# board.net
KiCad netlist of a schematic drawn in EAGLE
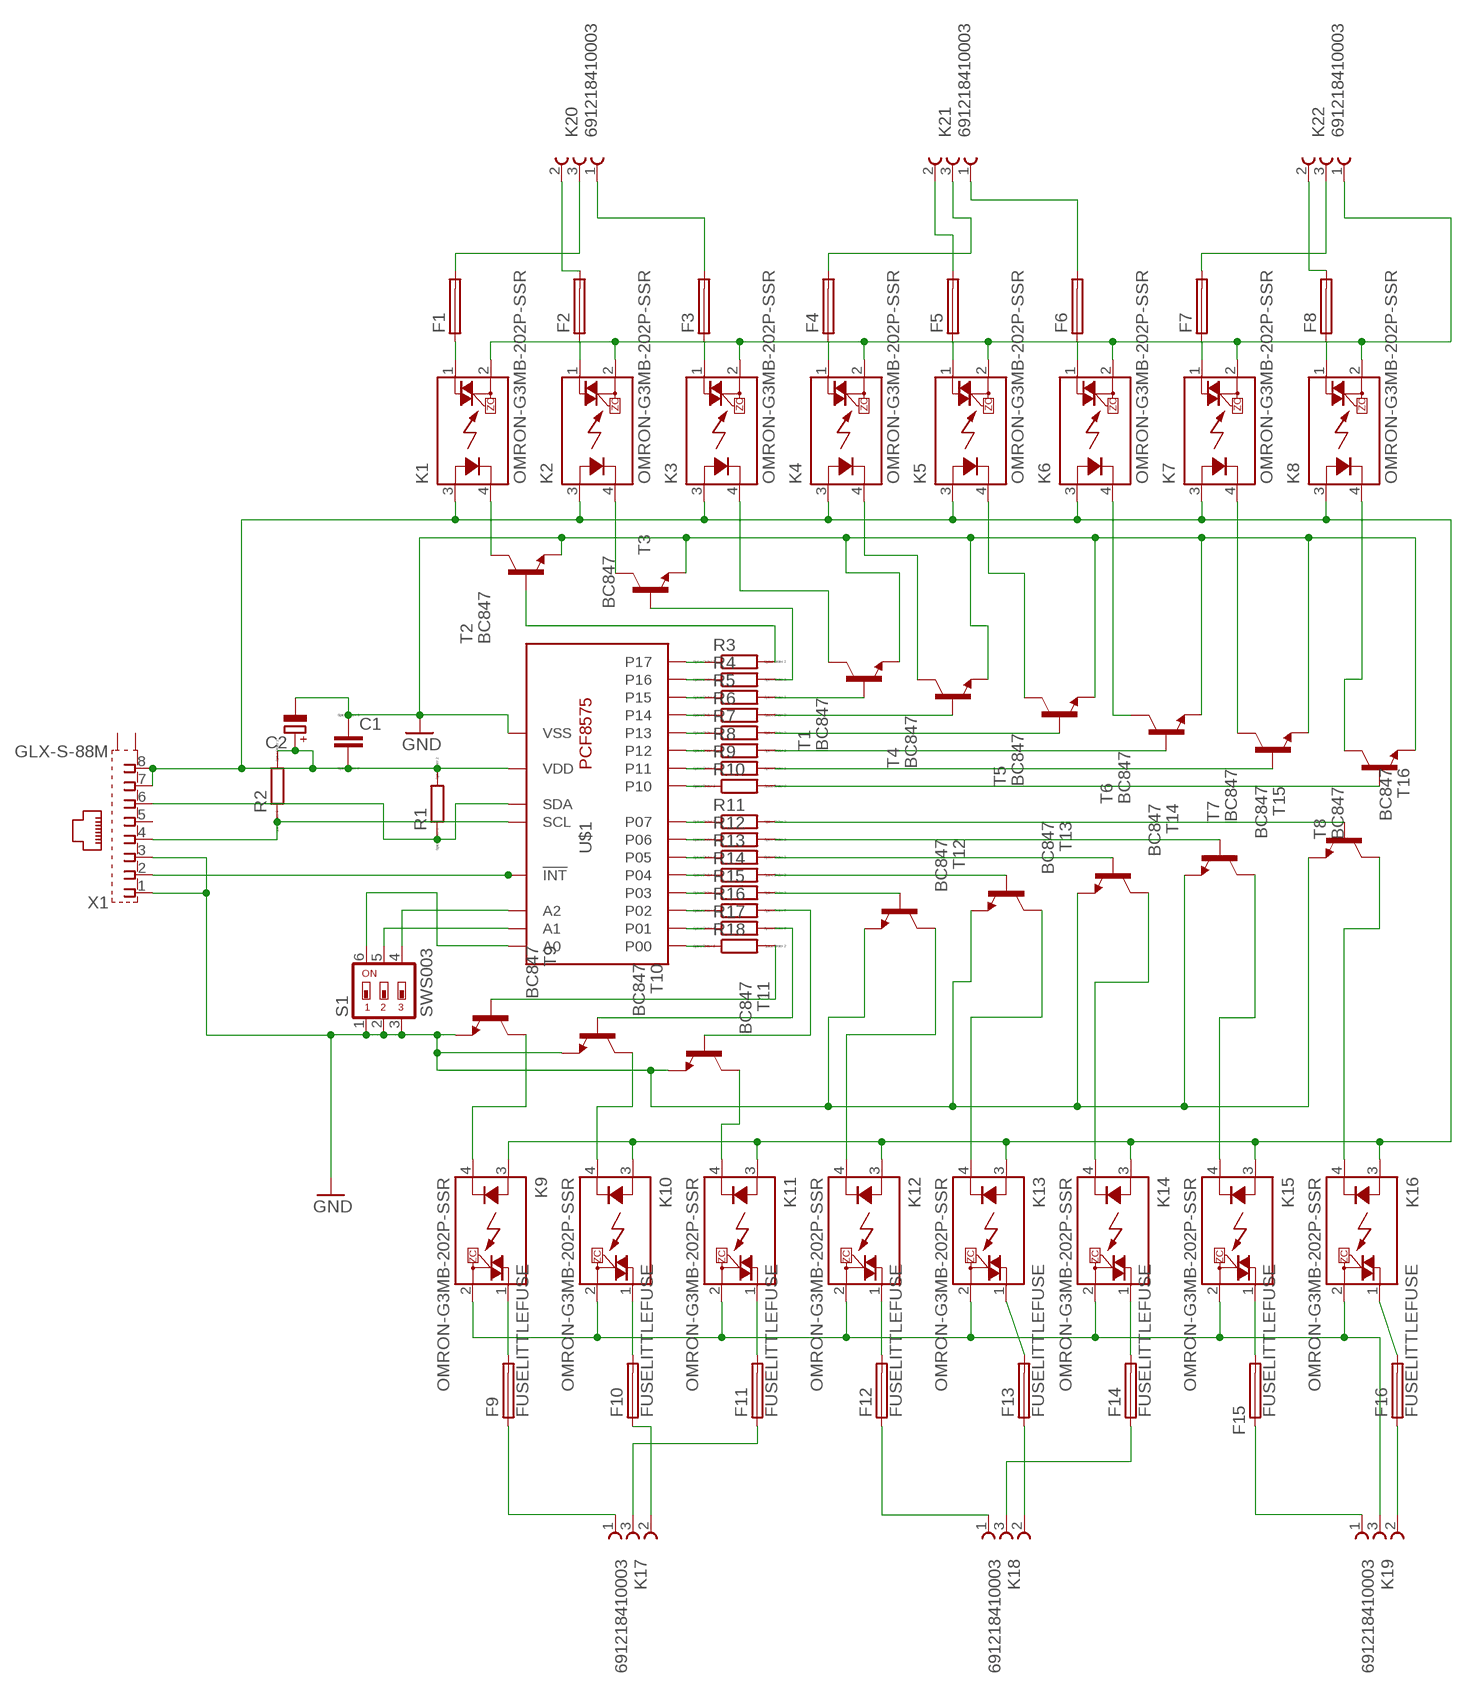
[diagram p0: schematic, sheet 1]

(export (version "E")
  (design (tool "Eeschema 10.0.6"))
  (components
    (comp (ref "C1")
      (value "CC1206")
      (footprint "eagle-import:C1206")
      (libsource (lib "eagle-import") (part "CC1206"))
    )
    (comp (ref "C2")
      (value "CPOL-EU150CLZ-0810")
      (footprint "eagle-import:150CLZ-0810")
      (libsource (lib "eagle-import") (part "CPOL-EU150CLZ-0810"))
    )
    (comp (ref "F1")
      (value "FUSELITTLEFUSE")
      (footprint "eagle-import:LITTLEFUSE")
      (libsource (lib "eagle-import") (part "FUSELITTLEFUSE"))
    )
    (comp (ref "F2")
      (value "FUSELITTLEFUSE")
      (footprint "eagle-import:LITTLEFUSE")
      (libsource (lib "eagle-import") (part "FUSELITTLEFUSE"))
    )
    (comp (ref "F3")
      (value "FUSELITTLEFUSE")
      (footprint "eagle-import:LITTLEFUSE")
      (libsource (lib "eagle-import") (part "FUSELITTLEFUSE"))
    )
    (comp (ref "F4")
      (value "FUSELITTLEFUSE")
      (footprint "eagle-import:LITTLEFUSE")
      (libsource (lib "eagle-import") (part "FUSELITTLEFUSE"))
    )
    (comp (ref "F5")
      (value "FUSELITTLEFUSE")
      (footprint "eagle-import:LITTLEFUSE")
      (libsource (lib "eagle-import") (part "FUSELITTLEFUSE"))
    )
    (comp (ref "F6")
      (value "FUSELITTLEFUSE")
      (footprint "eagle-import:LITTLEFUSE")
      (libsource (lib "eagle-import") (part "FUSELITTLEFUSE"))
    )
    (comp (ref "F7")
      (value "FUSELITTLEFUSE")
      (footprint "eagle-import:LITTLEFUSE")
      (libsource (lib "eagle-import") (part "FUSELITTLEFUSE"))
    )
    (comp (ref "F8")
      (value "FUSELITTLEFUSE")
      (footprint "eagle-import:LITTLEFUSE")
      (libsource (lib "eagle-import") (part "FUSELITTLEFUSE"))
    )
    (comp (ref "F9")
      (value "FUSELITTLEFUSE")
      (footprint "eagle-import:LITTLEFUSE")
      (libsource (lib "eagle-import") (part "FUSELITTLEFUSE"))
    )
    (comp (ref "F10")
      (value "FUSELITTLEFUSE")
      (footprint "eagle-import:LITTLEFUSE")
      (libsource (lib "eagle-import") (part "FUSELITTLEFUSE"))
    )
    (comp (ref "F11")
      (value "FUSELITTLEFUSE")
      (footprint "eagle-import:LITTLEFUSE")
      (libsource (lib "eagle-import") (part "FUSELITTLEFUSE"))
    )
    (comp (ref "F12")
      (value "FUSELITTLEFUSE")
      (footprint "eagle-import:LITTLEFUSE")
      (libsource (lib "eagle-import") (part "FUSELITTLEFUSE"))
    )
    (comp (ref "F13")
      (value "FUSELITTLEFUSE")
      (footprint "eagle-import:LITTLEFUSE")
      (libsource (lib "eagle-import") (part "FUSELITTLEFUSE"))
    )
    (comp (ref "F14")
      (value "FUSELITTLEFUSE")
      (footprint "eagle-import:LITTLEFUSE")
      (libsource (lib "eagle-import") (part "FUSELITTLEFUSE"))
    )
    (comp (ref "F15")
      (value "FUSELITTLEFUSE")
      (footprint "eagle-import:LITTLEFUSE")
      (libsource (lib "eagle-import") (part "FUSELITTLEFUSE"))
    )
    (comp (ref "F16")
      (value "FUSELITTLEFUSE")
      (footprint "eagle-import:LITTLEFUSE")
      (libsource (lib "eagle-import") (part "FUSELITTLEFUSE"))
    )
    (comp (ref "K1")
      (value "OMRON-G3MB-202P-SSR")
      (footprint "eagle-import:OMRON-G3MB-202P-SSR")
      (libsource (lib "eagle-import") (part "OMRON-G3MB-202P-SSR"))
    )
    (comp (ref "K2")
      (value "OMRON-G3MB-202P-SSR")
      (footprint "eagle-import:OMRON-G3MB-202P-SSR")
      (libsource (lib "eagle-import") (part "OMRON-G3MB-202P-SSR"))
    )
    (comp (ref "K3")
      (value "OMRON-G3MB-202P-SSR")
      (footprint "eagle-import:OMRON-G3MB-202P-SSR")
      (libsource (lib "eagle-import") (part "OMRON-G3MB-202P-SSR"))
    )
    (comp (ref "K4")
      (value "OMRON-G3MB-202P-SSR")
      (footprint "eagle-import:OMRON-G3MB-202P-SSR")
      (libsource (lib "eagle-import") (part "OMRON-G3MB-202P-SSR"))
    )
    (comp (ref "K5")
      (value "OMRON-G3MB-202P-SSR")
      (footprint "eagle-import:OMRON-G3MB-202P-SSR")
      (libsource (lib "eagle-import") (part "OMRON-G3MB-202P-SSR"))
    )
    (comp (ref "K6")
      (value "OMRON-G3MB-202P-SSR")
      (footprint "eagle-import:OMRON-G3MB-202P-SSR")
      (libsource (lib "eagle-import") (part "OMRON-G3MB-202P-SSR"))
    )
    (comp (ref "K7")
      (value "OMRON-G3MB-202P-SSR")
      (footprint "eagle-import:OMRON-G3MB-202P-SSR")
      (libsource (lib "eagle-import") (part "OMRON-G3MB-202P-SSR"))
    )
    (comp (ref "K8")
      (value "OMRON-G3MB-202P-SSR")
      (footprint "eagle-import:OMRON-G3MB-202P-SSR")
      (libsource (lib "eagle-import") (part "OMRON-G3MB-202P-SSR"))
    )
    (comp (ref "K9")
      (value "OMRON-G3MB-202P-SSR")
      (footprint "eagle-import:OMRON-G3MB-202P-SSR")
      (libsource (lib "eagle-import") (part "OMRON-G3MB-202P-SSR"))
    )
    (comp (ref "K10")
      (value "OMRON-G3MB-202P-SSR")
      (footprint "eagle-import:OMRON-G3MB-202P-SSR")
      (libsource (lib "eagle-import") (part "OMRON-G3MB-202P-SSR"))
    )
    (comp (ref "K11")
      (value "OMRON-G3MB-202P-SSR")
      (footprint "eagle-import:OMRON-G3MB-202P-SSR")
      (libsource (lib "eagle-import") (part "OMRON-G3MB-202P-SSR"))
    )
    (comp (ref "K12")
      (value "OMRON-G3MB-202P-SSR")
      (footprint "eagle-import:OMRON-G3MB-202P-SSR")
      (libsource (lib "eagle-import") (part "OMRON-G3MB-202P-SSR"))
    )
    (comp (ref "K13")
      (value "OMRON-G3MB-202P-SSR")
      (footprint "eagle-import:OMRON-G3MB-202P-SSR")
      (libsource (lib "eagle-import") (part "OMRON-G3MB-202P-SSR"))
    )
    (comp (ref "K14")
      (value "OMRON-G3MB-202P-SSR")
      (footprint "eagle-import:OMRON-G3MB-202P-SSR")
      (libsource (lib "eagle-import") (part "OMRON-G3MB-202P-SSR"))
    )
    (comp (ref "K15")
      (value "OMRON-G3MB-202P-SSR")
      (footprint "eagle-import:OMRON-G3MB-202P-SSR")
      (libsource (lib "eagle-import") (part "OMRON-G3MB-202P-SSR"))
    )
    (comp (ref "K16")
      (value "OMRON-G3MB-202P-SSR")
      (footprint "eagle-import:OMRON-G3MB-202P-SSR")
      (libsource (lib "eagle-import") (part "OMRON-G3MB-202P-SSR"))
    )
    (comp (ref "K17")
      (value "691218410003")
      (footprint "eagle-import:691218410003")
      (libsource (lib "eagle-import") (part "691218410003"))
    )
    (comp (ref "K18")
      (value "691218410003")
      (footprint "eagle-import:691218410003")
      (libsource (lib "eagle-import") (part "691218410003"))
    )
    (comp (ref "K19")
      (value "691218410003")
      (footprint "eagle-import:691218410003")
      (libsource (lib "eagle-import") (part "691218410003"))
    )
    (comp (ref "K20")
      (value "691218410003")
      (footprint "eagle-import:691218410003")
      (libsource (lib "eagle-import") (part "691218410003"))
    )
    (comp (ref "K21")
      (value "691218410003")
      (footprint "eagle-import:691218410003")
      (libsource (lib "eagle-import") (part "691218410003"))
    )
    (comp (ref "K22")
      (value "691218410003")
      (footprint "eagle-import:691218410003")
      (libsource (lib "eagle-import") (part "691218410003"))
    )
    (comp (ref "R1")
      (value "RR1206")
      (footprint "eagle-import:R1206")
      (libsource (lib "eagle-import") (part "RR1206"))
    )
    (comp (ref "R2")
      (value "RR1206")
      (footprint "eagle-import:R1206")
      (libsource (lib "eagle-import") (part "RR1206"))
    )
    (comp (ref "R3")
      (value "RR1206")
      (footprint "eagle-import:R1206")
      (libsource (lib "eagle-import") (part "RR1206"))
    )
    (comp (ref "R4")
      (value "RR1206")
      (footprint "eagle-import:R1206")
      (libsource (lib "eagle-import") (part "RR1206"))
    )
    (comp (ref "R5")
      (value "RR1206")
      (footprint "eagle-import:R1206")
      (libsource (lib "eagle-import") (part "RR1206"))
    )
    (comp (ref "R6")
      (value "RR1206")
      (footprint "eagle-import:R1206")
      (libsource (lib "eagle-import") (part "RR1206"))
    )
    (comp (ref "R7")
      (value "RR1206")
      (footprint "eagle-import:R1206")
      (libsource (lib "eagle-import") (part "RR1206"))
    )
    (comp (ref "R8")
      (value "RR1206")
      (footprint "eagle-import:R1206")
      (libsource (lib "eagle-import") (part "RR1206"))
    )
    (comp (ref "R9")
      (value "RR1206")
      (footprint "eagle-import:R1206")
      (libsource (lib "eagle-import") (part "RR1206"))
    )
    (comp (ref "R10")
      (value "RR1206")
      (footprint "eagle-import:R1206")
      (libsource (lib "eagle-import") (part "RR1206"))
    )
    (comp (ref "R11")
      (value "RR1206")
      (footprint "eagle-import:R1206")
      (libsource (lib "eagle-import") (part "RR1206"))
    )
    (comp (ref "R12")
      (value "RR1206")
      (footprint "eagle-import:R1206")
      (libsource (lib "eagle-import") (part "RR1206"))
    )
    (comp (ref "R13")
      (value "RR1206")
      (footprint "eagle-import:R1206")
      (libsource (lib "eagle-import") (part "RR1206"))
    )
    (comp (ref "R14")
      (value "RR1206")
      (footprint "eagle-import:R1206")
      (libsource (lib "eagle-import") (part "RR1206"))
    )
    (comp (ref "R15")
      (value "RR1206")
      (footprint "eagle-import:R1206")
      (libsource (lib "eagle-import") (part "RR1206"))
    )
    (comp (ref "R16")
      (value "RR1206")
      (footprint "eagle-import:R1206")
      (libsource (lib "eagle-import") (part "RR1206"))
    )
    (comp (ref "R17")
      (value "RR1206")
      (footprint "eagle-import:R1206")
      (libsource (lib "eagle-import") (part "RR1206"))
    )
    (comp (ref "R18")
      (value "RR1206")
      (footprint "eagle-import:R1206")
      (libsource (lib "eagle-import") (part "RR1206"))
    )
    (comp (ref "S1")
      (value "SWS003")
      (footprint "eagle-import:SMS-003")
      (libsource (lib "eagle-import") (part "SWS003"))
    )
    (comp (ref "T1")
      (value "BC847")
      (footprint "eagle-import:SOT23")
      (libsource (lib "eagle-import") (part "BC847"))
    )
    (comp (ref "T2")
      (value "BC847")
      (footprint "eagle-import:SOT23")
      (libsource (lib "eagle-import") (part "BC847"))
    )
    (comp (ref "T3")
      (value "BC847")
      (footprint "eagle-import:SOT23")
      (libsource (lib "eagle-import") (part "BC847"))
    )
    (comp (ref "T4")
      (value "BC847")
      (footprint "eagle-import:SOT23")
      (libsource (lib "eagle-import") (part "BC847"))
    )
    (comp (ref "T5")
      (value "BC847")
      (footprint "eagle-import:SOT23")
      (libsource (lib "eagle-import") (part "BC847"))
    )
    (comp (ref "T6")
      (value "BC847")
      (footprint "eagle-import:SOT23")
      (libsource (lib "eagle-import") (part "BC847"))
    )
    (comp (ref "T7")
      (value "BC847")
      (footprint "eagle-import:SOT23")
      (libsource (lib "eagle-import") (part "BC847"))
    )
    (comp (ref "T8")
      (value "BC847")
      (footprint "eagle-import:SOT23")
      (libsource (lib "eagle-import") (part "BC847"))
    )
    (comp (ref "T9")
      (value "BC847")
      (footprint "eagle-import:SOT23")
      (libsource (lib "eagle-import") (part "BC847"))
    )
    (comp (ref "T10")
      (value "BC847")
      (footprint "eagle-import:SOT23")
      (libsource (lib "eagle-import") (part "BC847"))
    )
    (comp (ref "T11")
      (value "BC847")
      (footprint "eagle-import:SOT23")
      (libsource (lib "eagle-import") (part "BC847"))
    )
    (comp (ref "T12")
      (value "BC847")
      (footprint "eagle-import:SOT23")
      (libsource (lib "eagle-import") (part "BC847"))
    )
    (comp (ref "T13")
      (value "BC847")
      (footprint "eagle-import:SOT23")
      (libsource (lib "eagle-import") (part "BC847"))
    )
    (comp (ref "T14")
      (value "BC847")
      (footprint "eagle-import:SOT23")
      (libsource (lib "eagle-import") (part "BC847"))
    )
    (comp (ref "T15")
      (value "BC847")
      (footprint "eagle-import:SOT23")
      (libsource (lib "eagle-import") (part "BC847"))
    )
    (comp (ref "T16")
      (value "BC847")
      (footprint "eagle-import:SOT23")
      (libsource (lib "eagle-import") (part "BC847"))
    )
    (comp (ref "U$1")
      (value "PCF8575CSSOP24")
      (footprint "eagle-import:SOP65P775X200-24N")
      (libsource (lib "eagle-import") (part "PCF8575CSSOP24"))
    )
    (comp (ref "X1")
      (value "GLX-S-88M")
      (footprint "eagle-import:GLX-S-88M")
      (libsource (lib "eagle-import") (part "GLX-S-88M"))
    )
  )
  (nets
    (net (code "1") (name "GND") (class "Default")
      (node (ref "C1") (pin "1") (pinfunction "1_1") (pintype "passive"))
      (node (ref "C2") (pin "-") (pinfunction "-_-") (pintype "passive"))
      (node (ref "S1") (pin "1") (pinfunction "1_1") (pintype "passive"))
      (node (ref "S1") (pin "2") (pinfunction "2_2") (pintype "passive"))
      (node (ref "S1") (pin "3") (pinfunction "3_3") (pintype "passive"))
      (node (ref "T1") (pin "2") (pinfunction "E_2") (pintype "passive"))
      (node (ref "T10") (pin "2") (pinfunction "E_2") (pintype "passive"))
      (node (ref "T11") (pin "2") (pinfunction "E_2") (pintype "passive"))
      (node (ref "T12") (pin "2") (pinfunction "E_2") (pintype "passive"))
      (node (ref "T13") (pin "2") (pinfunction "E_2") (pintype "passive"))
      (node (ref "T14") (pin "2") (pinfunction "E_2") (pintype "passive"))
      (node (ref "T15") (pin "2") (pinfunction "E_2") (pintype "passive"))
      (node (ref "T16") (pin "2") (pinfunction "E_2") (pintype "passive"))
      (node (ref "T2") (pin "2") (pinfunction "E_2") (pintype "passive"))
      (node (ref "T3") (pin "2") (pinfunction "E_2") (pintype "passive"))
      (node (ref "T4") (pin "2") (pinfunction "E_2") (pintype "passive"))
      (node (ref "T5") (pin "2") (pinfunction "E_2") (pintype "passive"))
      (node (ref "T6") (pin "2") (pinfunction "E_2") (pintype "passive"))
      (node (ref "T7") (pin "2") (pinfunction "E_2") (pintype "passive"))
      (node (ref "T8") (pin "2") (pinfunction "E_2") (pintype "passive"))
      (node (ref "T9") (pin "2") (pinfunction "E_2") (pintype "passive"))
      (node (ref "U$1") (pin "12") (pinfunction "VSS_12") (pintype "power_in"))
      (node (ref "X1") (pin "1") (pinfunction "1_1") (pintype "passive"))
      (node (ref "X1") (pin "3") (pinfunction "3_3") (pintype "passive"))
    )
    (net (code "2") (name "Net-(K1-A)") (class "Default")
      (node (ref "C1") (pin "2") (pinfunction "2_2") (pintype "passive"))
      (node (ref "C2") (pin "+") (pinfunction "+_+") (pintype "passive"))
      (node (ref "K1") (pin "3") (pinfunction "A_3") (pintype "passive"))
      (node (ref "K10") (pin "3") (pinfunction "A_3") (pintype "passive"))
      (node (ref "K11") (pin "3") (pinfunction "A_3") (pintype "passive"))
      (node (ref "K12") (pin "3") (pinfunction "A_3") (pintype "passive"))
      (node (ref "K13") (pin "3") (pinfunction "A_3") (pintype "passive"))
      (node (ref "K14") (pin "3") (pinfunction "A_3") (pintype "passive"))
      (node (ref "K15") (pin "3") (pinfunction "A_3") (pintype "passive"))
      (node (ref "K16") (pin "3") (pinfunction "A_3") (pintype "passive"))
      (node (ref "K2") (pin "3") (pinfunction "A_3") (pintype "passive"))
      (node (ref "K3") (pin "3") (pinfunction "A_3") (pintype "passive"))
      (node (ref "K4") (pin "3") (pinfunction "A_3") (pintype "passive"))
      (node (ref "K5") (pin "3") (pinfunction "A_3") (pintype "passive"))
      (node (ref "K6") (pin "3") (pinfunction "A_3") (pintype "passive"))
      (node (ref "K7") (pin "3") (pinfunction "A_3") (pintype "passive"))
      (node (ref "K8") (pin "3") (pinfunction "A_3") (pintype "passive"))
      (node (ref "K9") (pin "3") (pinfunction "A_3") (pintype "passive"))
      (node (ref "R1") (pin "2") (pinfunction "2_2") (pintype "passive"))
      (node (ref "R2") (pin "2") (pinfunction "2_2") (pintype "passive"))
      (node (ref "U$1") (pin "24") (pinfunction "VDD_24") (pintype "power_in"))
      (node (ref "X1") (pin "7") (pinfunction "7_7") (pintype "passive"))
      (node (ref "X1") (pin "8") (pinfunction "8_8") (pintype "passive"))
    )
    (net (code "3") (name "Net-(K1-DS1)") (class "Default")
      (node (ref "F1") (pin "1") (pinfunction "1_1") (pintype "passive"))
      (node (ref "K1") (pin "1") (pinfunction "DS1_1") (pintype "passive"))
    )
    (net (code "4") (name "Net-(K1-DS2)") (class "Default")
      (node (ref "K1") (pin "2") (pinfunction "DS2_2") (pintype "passive"))
      (node (ref "K2") (pin "2") (pinfunction "DS2_2") (pintype "passive"))
      (node (ref "K22") (pin "1") (pinfunction "3_1") (pintype "passive"))
      (node (ref "K3") (pin "2") (pinfunction "DS2_2") (pintype "passive"))
      (node (ref "K4") (pin "2") (pinfunction "DS2_2") (pintype "passive"))
      (node (ref "K5") (pin "2") (pinfunction "DS2_2") (pintype "passive"))
      (node (ref "K6") (pin "2") (pinfunction "DS2_2") (pintype "passive"))
      (node (ref "K7") (pin "2") (pinfunction "DS2_2") (pintype "passive"))
      (node (ref "K8") (pin "2") (pinfunction "DS2_2") (pintype "passive"))
    )
    (net (code "5") (name "Net-(K1-K)") (class "Default")
      (node (ref "K1") (pin "4") (pinfunction "K_4") (pintype "passive"))
      (node (ref "T2") (pin "3") (pinfunction "C_3") (pintype "passive"))
    )
    (net (code "6") (name "Net-(K2-DS1)") (class "Default")
      (node (ref "F2") (pin "1") (pinfunction "1_1") (pintype "passive"))
      (node (ref "K2") (pin "1") (pinfunction "DS1_1") (pintype "passive"))
    )
    (net (code "7") (name "Net-(K2-K)") (class "Default")
      (node (ref "K2") (pin "4") (pinfunction "K_4") (pintype "passive"))
      (node (ref "T3") (pin "3") (pinfunction "C_3") (pintype "passive"))
    )
    (net (code "8") (name "Net-(K3-DS1)") (class "Default")
      (node (ref "F3") (pin "1") (pinfunction "1_1") (pintype "passive"))
      (node (ref "K3") (pin "1") (pinfunction "DS1_1") (pintype "passive"))
    )
    (net (code "9") (name "Net-(K3-K)") (class "Default")
      (node (ref "K3") (pin "4") (pinfunction "K_4") (pintype "passive"))
      (node (ref "T1") (pin "3") (pinfunction "C_3") (pintype "passive"))
    )
    (net (code "10") (name "Net-(K4-DS1)") (class "Default")
      (node (ref "F4") (pin "1") (pinfunction "1_1") (pintype "passive"))
      (node (ref "K4") (pin "1") (pinfunction "DS1_1") (pintype "passive"))
    )
    (net (code "11") (name "Net-(K4-K)") (class "Default")
      (node (ref "K4") (pin "4") (pinfunction "K_4") (pintype "passive"))
      (node (ref "T4") (pin "3") (pinfunction "C_3") (pintype "passive"))
    )
    (net (code "12") (name "Net-(K5-DS1)") (class "Default")
      (node (ref "F5") (pin "1") (pinfunction "1_1") (pintype "passive"))
      (node (ref "K5") (pin "1") (pinfunction "DS1_1") (pintype "passive"))
    )
    (net (code "13") (name "Net-(K5-K)") (class "Default")
      (node (ref "K5") (pin "4") (pinfunction "K_4") (pintype "passive"))
      (node (ref "T5") (pin "3") (pinfunction "C_3") (pintype "passive"))
    )
    (net (code "14") (name "Net-(K6-DS1)") (class "Default")
      (node (ref "F6") (pin "1") (pinfunction "1_1") (pintype "passive"))
      (node (ref "K6") (pin "1") (pinfunction "DS1_1") (pintype "passive"))
    )
    (net (code "15") (name "Net-(K6-K)") (class "Default")
      (node (ref "K6") (pin "4") (pinfunction "K_4") (pintype "passive"))
      (node (ref "T6") (pin "3") (pinfunction "C_3") (pintype "passive"))
    )
    (net (code "16") (name "Net-(K7-DS1)") (class "Default")
      (node (ref "F7") (pin "1") (pinfunction "1_1") (pintype "passive"))
      (node (ref "K7") (pin "1") (pinfunction "DS1_1") (pintype "passive"))
    )
    (net (code "17") (name "Net-(K7-K)") (class "Default")
      (node (ref "K7") (pin "4") (pinfunction "K_4") (pintype "passive"))
      (node (ref "T7") (pin "3") (pinfunction "C_3") (pintype "passive"))
    )
    (net (code "18") (name "Net-(K8-DS1)") (class "Default")
      (node (ref "F8") (pin "1") (pinfunction "1_1") (pintype "passive"))
      (node (ref "K8") (pin "1") (pinfunction "DS1_1") (pintype "passive"))
    )
    (net (code "19") (name "Net-(K8-K)") (class "Default")
      (node (ref "K8") (pin "4") (pinfunction "K_4") (pintype "passive"))
      (node (ref "T8") (pin "3") (pinfunction "C_3") (pintype "passive"))
    )
    (net (code "20") (name "Net-(K9-DS1)") (class "Default")
      (node (ref "F9") (pin "2") (pinfunction "2_2") (pintype "passive"))
      (node (ref "K9") (pin "1") (pinfunction "DS1_1") (pintype "passive"))
    )
    (net (code "21") (name "Net-(K9-K)") (class "Default")
      (node (ref "K9") (pin "4") (pinfunction "K_4") (pintype "passive"))
      (node (ref "T9") (pin "3") (pinfunction "C_3") (pintype "passive"))
    )
    (net (code "22") (name "Net-(K10-DS1)") (class "Default")
      (node (ref "F10") (pin "2") (pinfunction "2_2") (pintype "passive"))
      (node (ref "K10") (pin "1") (pinfunction "DS1_1") (pintype "passive"))
    )
    (net (code "23") (name "Net-(K10-DS2)") (class "Default")
      (node (ref "K10") (pin "2") (pinfunction "DS2_2") (pintype "passive"))
      (node (ref "K11") (pin "2") (pinfunction "DS2_2") (pintype "passive"))
      (node (ref "K12") (pin "2") (pinfunction "DS2_2") (pintype "passive"))
      (node (ref "K13") (pin "2") (pinfunction "DS2_2") (pintype "passive"))
      (node (ref "K14") (pin "2") (pinfunction "DS2_2") (pintype "passive"))
      (node (ref "K15") (pin "2") (pinfunction "DS2_2") (pintype "passive"))
      (node (ref "K16") (pin "2") (pinfunction "DS2_2") (pintype "passive"))
      (node (ref "K19") (pin "3") (pinfunction "2_3") (pintype "passive"))
      (node (ref "K9") (pin "2") (pinfunction "DS2_2") (pintype "passive"))
    )
    (net (code "24") (name "Net-(K10-K)") (class "Default")
      (node (ref "K10") (pin "4") (pinfunction "K_4") (pintype "passive"))
      (node (ref "T10") (pin "3") (pinfunction "C_3") (pintype "passive"))
    )
    (net (code "25") (name "Net-(K11-DS1)") (class "Default")
      (node (ref "F11") (pin "2") (pinfunction "2_2") (pintype "passive"))
      (node (ref "K11") (pin "1") (pinfunction "DS1_1") (pintype "passive"))
    )
    (net (code "26") (name "Net-(K11-K)") (class "Default")
      (node (ref "K11") (pin "4") (pinfunction "K_4") (pintype "passive"))
      (node (ref "T11") (pin "3") (pinfunction "C_3") (pintype "passive"))
    )
    (net (code "27") (name "Net-(K12-DS1)") (class "Default")
      (node (ref "F12") (pin "2") (pinfunction "2_2") (pintype "passive"))
      (node (ref "K12") (pin "1") (pinfunction "DS1_1") (pintype "passive"))
    )
    (net (code "28") (name "Net-(K12-K)") (class "Default")
      (node (ref "K12") (pin "4") (pinfunction "K_4") (pintype "passive"))
      (node (ref "T12") (pin "3") (pinfunction "C_3") (pintype "passive"))
    )
    (net (code "29") (name "Net-(K13-DS1)") (class "Default")
      (node (ref "F13") (pin "2") (pinfunction "2_2") (pintype "passive"))
      (node (ref "K13") (pin "1") (pinfunction "DS1_1") (pintype "passive"))
    )
    (net (code "30") (name "Net-(K13-K)") (class "Default")
      (node (ref "K13") (pin "4") (pinfunction "K_4") (pintype "passive"))
      (node (ref "T13") (pin "3") (pinfunction "C_3") (pintype "passive"))
    )
    (net (code "31") (name "Net-(K14-DS1)") (class "Default")
      (node (ref "F14") (pin "2") (pinfunction "2_2") (pintype "passive"))
      (node (ref "K14") (pin "1") (pinfunction "DS1_1") (pintype "passive"))
    )
    (net (code "32") (name "Net-(K14-K)") (class "Default")
      (node (ref "K14") (pin "4") (pinfunction "K_4") (pintype "passive"))
      (node (ref "T14") (pin "3") (pinfunction "C_3") (pintype "passive"))
    )
    (net (code "33") (name "Net-(K15-DS1)") (class "Default")
      (node (ref "F15") (pin "2") (pinfunction "2_2") (pintype "passive"))
      (node (ref "K15") (pin "1") (pinfunction "DS1_1") (pintype "passive"))
    )
    (net (code "34") (name "Net-(K15-K)") (class "Default")
      (node (ref "K15") (pin "4") (pinfunction "K_4") (pintype "passive"))
      (node (ref "T15") (pin "3") (pinfunction "C_3") (pintype "passive"))
    )
    (net (code "35") (name "Net-(K16-DS1)") (class "Default")
      (node (ref "F16") (pin "2") (pinfunction "2_2") (pintype "passive"))
      (node (ref "K16") (pin "1") (pinfunction "DS1_1") (pintype "passive"))
    )
    (net (code "36") (name "Net-(K16-K)") (class "Default")
      (node (ref "K16") (pin "4") (pinfunction "K_4") (pintype "passive"))
      (node (ref "T16") (pin "3") (pinfunction "C_3") (pintype "passive"))
    )
    (net (code "37") (name "Net-(K17-1)") (class "Default")
      (node (ref "F10") (pin "1") (pinfunction "1_1") (pintype "passive"))
      (node (ref "K17") (pin "2") (pinfunction "1_2") (pintype "passive"))
    )
    (net (code "38") (name "Net-(K17-2)") (class "Default")
      (node (ref "F11") (pin "1") (pinfunction "1_1") (pintype "passive"))
      (node (ref "K17") (pin "3") (pinfunction "2_3") (pintype "passive"))
    )
    (net (code "39") (name "Net-(K17-3)") (class "Default")
      (node (ref "F9") (pin "1") (pinfunction "1_1") (pintype "passive"))
      (node (ref "K17") (pin "1") (pinfunction "3_1") (pintype "passive"))
    )
    (net (code "40") (name "Net-(K18-1)") (class "Default")
      (node (ref "F13") (pin "1") (pinfunction "1_1") (pintype "passive"))
      (node (ref "K18") (pin "2") (pinfunction "1_2") (pintype "passive"))
    )
    (net (code "41") (name "Net-(K18-2)") (class "Default")
      (node (ref "F14") (pin "1") (pinfunction "1_1") (pintype "passive"))
      (node (ref "K18") (pin "3") (pinfunction "2_3") (pintype "passive"))
    )
    (net (code "42") (name "Net-(K18-3)") (class "Default")
      (node (ref "F12") (pin "1") (pinfunction "1_1") (pintype "passive"))
      (node (ref "K18") (pin "1") (pinfunction "3_1") (pintype "passive"))
    )
    (net (code "43") (name "Net-(K19-1)") (class "Default")
      (node (ref "F16") (pin "1") (pinfunction "1_1") (pintype "passive"))
      (node (ref "K19") (pin "2") (pinfunction "1_2") (pintype "passive"))
    )
    (net (code "44") (name "Net-(K19-3)") (class "Default")
      (node (ref "F15") (pin "1") (pinfunction "1_1") (pintype "passive"))
      (node (ref "K19") (pin "1") (pinfunction "3_1") (pintype "passive"))
    )
    (net (code "45") (name "Net-(K20-1)") (class "Default")
      (node (ref "F2") (pin "2") (pinfunction "2_2") (pintype "passive"))
      (node (ref "K20") (pin "2") (pinfunction "1_2") (pintype "passive"))
    )
    (net (code "46") (name "Net-(K20-2)") (class "Default")
      (node (ref "F1") (pin "2") (pinfunction "2_2") (pintype "passive"))
      (node (ref "K20") (pin "3") (pinfunction "2_3") (pintype "passive"))
    )
    (net (code "47") (name "Net-(K20-3)") (class "Default")
      (node (ref "F3") (pin "2") (pinfunction "2_2") (pintype "passive"))
      (node (ref "K20") (pin "1") (pinfunction "3_1") (pintype "passive"))
    )
    (net (code "48") (name "Net-(K21-1)") (class "Default")
      (node (ref "F5") (pin "2") (pinfunction "2_2") (pintype "passive"))
      (node (ref "K21") (pin "2") (pinfunction "1_2") (pintype "passive"))
    )
    (net (code "49") (name "Net-(K21-2)") (class "Default")
      (node (ref "F4") (pin "2") (pinfunction "2_2") (pintype "passive"))
      (node (ref "K21") (pin "3") (pinfunction "2_3") (pintype "passive"))
    )
    (net (code "50") (name "Net-(K21-3)") (class "Default")
      (node (ref "F6") (pin "2") (pinfunction "2_2") (pintype "passive"))
      (node (ref "K21") (pin "1") (pinfunction "3_1") (pintype "passive"))
    )
    (net (code "51") (name "Net-(K22-1)") (class "Default")
      (node (ref "F8") (pin "2") (pinfunction "2_2") (pintype "passive"))
      (node (ref "K22") (pin "2") (pinfunction "1_2") (pintype "passive"))
    )
    (net (code "52") (name "Net-(K22-2)") (class "Default")
      (node (ref "F7") (pin "2") (pinfunction "2_2") (pintype "passive"))
      (node (ref "K22") (pin "3") (pinfunction "2_3") (pintype "passive"))
    )
    (net (code "53") (name "Net-(T1-B)") (class "Default")
      (node (ref "R5") (pin "2") (pinfunction "2_2") (pintype "passive"))
      (node (ref "T1") (pin "1") (pinfunction "B_1") (pintype "passive"))
    )
    (net (code "54") (name "Net-(T2-B)") (class "Default")
      (node (ref "R3") (pin "2") (pinfunction "2_2") (pintype "passive"))
      (node (ref "T2") (pin "1") (pinfunction "B_1") (pintype "passive"))
    )
    (net (code "55") (name "Net-(T3-B)") (class "Default")
      (node (ref "R4") (pin "2") (pinfunction "2_2") (pintype "passive"))
      (node (ref "T3") (pin "1") (pinfunction "B_1") (pintype "passive"))
    )
    (net (code "56") (name "Net-(T4-B)") (class "Default")
      (node (ref "R6") (pin "2") (pinfunction "2_2") (pintype "passive"))
      (node (ref "T4") (pin "1") (pinfunction "B_1") (pintype "passive"))
    )
    (net (code "57") (name "Net-(T5-B)") (class "Default")
      (node (ref "R7") (pin "2") (pinfunction "2_2") (pintype "passive"))
      (node (ref "T5") (pin "1") (pinfunction "B_1") (pintype "passive"))
    )
    (net (code "58") (name "Net-(T6-B)") (class "Default")
      (node (ref "R8") (pin "2") (pinfunction "2_2") (pintype "passive"))
      (node (ref "T6") (pin "1") (pinfunction "B_1") (pintype "passive"))
    )
    (net (code "59") (name "Net-(T7-B)") (class "Default")
      (node (ref "R9") (pin "2") (pinfunction "2_2") (pintype "passive"))
      (node (ref "T7") (pin "1") (pinfunction "B_1") (pintype "passive"))
    )
    (net (code "60") (name "Net-(T8-B)") (class "Default")
      (node (ref "R10") (pin "2") (pinfunction "2_2") (pintype "passive"))
      (node (ref "T8") (pin "1") (pinfunction "B_1") (pintype "passive"))
    )
    (net (code "61") (name "Net-(T9-B)") (class "Default")
      (node (ref "R18") (pin "2") (pinfunction "2_2") (pintype "passive"))
      (node (ref "T9") (pin "1") (pinfunction "B_1") (pintype "passive"))
    )
    (net (code "62") (name "Net-(T10-B)") (class "Default")
      (node (ref "R17") (pin "2") (pinfunction "2_2") (pintype "passive"))
      (node (ref "T10") (pin "1") (pinfunction "B_1") (pintype "passive"))
    )
    (net (code "63") (name "Net-(T11-B)") (class "Default")
      (node (ref "R16") (pin "2") (pinfunction "2_2") (pintype "passive"))
      (node (ref "T11") (pin "1") (pinfunction "B_1") (pintype "passive"))
    )
    (net (code "64") (name "Net-(T12-B)") (class "Default")
      (node (ref "R15") (pin "2") (pinfunction "2_2") (pintype "passive"))
      (node (ref "T12") (pin "1") (pinfunction "B_1") (pintype "passive"))
    )
    (net (code "65") (name "Net-(T13-B)") (class "Default")
      (node (ref "R14") (pin "2") (pinfunction "2_2") (pintype "passive"))
      (node (ref "T13") (pin "1") (pinfunction "B_1") (pintype "passive"))
    )
    (net (code "66") (name "Net-(T14-B)") (class "Default")
      (node (ref "R13") (pin "2") (pinfunction "2_2") (pintype "passive"))
      (node (ref "T14") (pin "1") (pinfunction "B_1") (pintype "passive"))
    )
    (net (code "67") (name "Net-(T15-B)") (class "Default")
      (node (ref "R12") (pin "2") (pinfunction "2_2") (pintype "passive"))
      (node (ref "T15") (pin "1") (pinfunction "B_1") (pintype "passive"))
    )
    (net (code "68") (name "Net-(T16-B)") (class "Default")
      (node (ref "R11") (pin "2") (pinfunction "2_2") (pintype "passive"))
      (node (ref "T16") (pin "1") (pinfunction "B_1") (pintype "passive"))
    )
    (net (code "69") (name "Net-(U$1-A0)") (class "Default")
      (node (ref "S1") (pin "6") (pinfunction "6_6") (pintype "passive"))
      (node (ref "U$1") (pin "21") (pinfunction "A0_21") (pintype "input"))
    )
    (net (code "70") (name "Net-(U$1-A1)") (class "Default")
      (node (ref "S1") (pin "5") (pinfunction "5_5") (pintype "passive"))
      (node (ref "U$1") (pin "2") (pinfunction "A1_2") (pintype "input"))
    )
    (net (code "71") (name "Net-(U$1-A2)") (class "Default")
      (node (ref "S1") (pin "4") (pinfunction "4_4") (pintype "passive"))
      (node (ref "U$1") (pin "3") (pinfunction "A2_3") (pintype "input"))
    )
    (net (code "72") (name "Net-(U$1-P00)") (class "Default")
      (node (ref "R18") (pin "1") (pinfunction "1_1") (pintype "passive"))
      (node (ref "U$1") (pin "4") (pinfunction "P00_4") (pintype "bidirectional"))
    )
    (net (code "73") (name "Net-(U$1-P01)") (class "Default")
      (node (ref "R17") (pin "1") (pinfunction "1_1") (pintype "passive"))
      (node (ref "U$1") (pin "5") (pinfunction "P01_5") (pintype "bidirectional"))
    )
    (net (code "74") (name "Net-(U$1-P02)") (class "Default")
      (node (ref "R16") (pin "1") (pinfunction "1_1") (pintype "passive"))
      (node (ref "U$1") (pin "6") (pinfunction "P02_6") (pintype "bidirectional"))
    )
    (net (code "75") (name "Net-(U$1-P03)") (class "Default")
      (node (ref "R15") (pin "1") (pinfunction "1_1") (pintype "passive"))
      (node (ref "U$1") (pin "7") (pinfunction "P03_7") (pintype "bidirectional"))
    )
    (net (code "76") (name "Net-(U$1-P04)") (class "Default")
      (node (ref "R14") (pin "1") (pinfunction "1_1") (pintype "passive"))
      (node (ref "U$1") (pin "8") (pinfunction "P04_8") (pintype "bidirectional"))
    )
    (net (code "77") (name "Net-(U$1-P05)") (class "Default")
      (node (ref "R13") (pin "1") (pinfunction "1_1") (pintype "passive"))
      (node (ref "U$1") (pin "9") (pinfunction "P05_9") (pintype "bidirectional"))
    )
    (net (code "78") (name "Net-(U$1-P06)") (class "Default")
      (node (ref "R12") (pin "1") (pinfunction "1_1") (pintype "passive"))
      (node (ref "U$1") (pin "10") (pinfunction "P06_10") (pintype "bidirectional"))
    )
    (net (code "79") (name "Net-(U$1-P07)") (class "Default")
      (node (ref "R11") (pin "1") (pinfunction "1_1") (pintype "passive"))
      (node (ref "U$1") (pin "11") (pinfunction "P07_11") (pintype "bidirectional"))
    )
    (net (code "80") (name "Net-(U$1-P10)") (class "Default")
      (node (ref "R10") (pin "1") (pinfunction "1_1") (pintype "passive"))
      (node (ref "U$1") (pin "13") (pinfunction "P10_13") (pintype "bidirectional"))
    )
    (net (code "81") (name "Net-(U$1-P11)") (class "Default")
      (node (ref "R9") (pin "1") (pinfunction "1_1") (pintype "passive"))
      (node (ref "U$1") (pin "14") (pinfunction "P11_14") (pintype "bidirectional"))
    )
    (net (code "82") (name "Net-(U$1-P12)") (class "Default")
      (node (ref "R8") (pin "1") (pinfunction "1_1") (pintype "passive"))
      (node (ref "U$1") (pin "15") (pinfunction "P12_15") (pintype "bidirectional"))
    )
    (net (code "83") (name "Net-(U$1-P13)") (class "Default")
      (node (ref "R7") (pin "1") (pinfunction "1_1") (pintype "passive"))
      (node (ref "U$1") (pin "16") (pinfunction "P13_16") (pintype "bidirectional"))
    )
    (net (code "84") (name "Net-(U$1-P14)") (class "Default")
      (node (ref "R6") (pin "1") (pinfunction "1_1") (pintype "passive"))
      (node (ref "U$1") (pin "17") (pinfunction "P14_17") (pintype "bidirectional"))
    )
    (net (code "85") (name "Net-(U$1-P15)") (class "Default")
      (node (ref "R5") (pin "1") (pinfunction "1_1") (pintype "passive"))
      (node (ref "U$1") (pin "18") (pinfunction "P15_18") (pintype "bidirectional"))
    )
    (net (code "86") (name "Net-(U$1-P16)") (class "Default")
      (node (ref "R4") (pin "1") (pinfunction "1_1") (pintype "passive"))
      (node (ref "U$1") (pin "19") (pinfunction "P16_19") (pintype "bidirectional"))
    )
    (net (code "87") (name "Net-(U$1-P17)") (class "Default")
      (node (ref "R3") (pin "1") (pinfunction "1_1") (pintype "passive"))
      (node (ref "U$1") (pin "20") (pinfunction "P17_20") (pintype "bidirectional"))
    )
    (net (code "88") (name "Net-(U$1-SCL)") (class "Default")
      (node (ref "R2") (pin "1") (pinfunction "1_1") (pintype "passive"))
      (node (ref "U$1") (pin "22") (pinfunction "SCL_22") (pintype "input"))
      (node (ref "X1") (pin "4") (pinfunction "4_4") (pintype "passive"))
    )
    (net (code "89") (name "Net-(U$1-SDA)") (class "Default")
      (node (ref "R1") (pin "1") (pinfunction "1_1") (pintype "passive"))
      (node (ref "U$1") (pin "23") (pinfunction "SDA_23") (pintype "bidirectional"))
      (node (ref "X1") (pin "6") (pinfunction "6_6") (pintype "passive"))
    )
    (net (code "90") (name "Net-(U$1-~{INT})") (class "Default")
      (node (ref "U$1") (pin "1") (pinfunction "~{INT}_1") (pintype "open_collector"))
      (node (ref "X1") (pin "2") (pinfunction "2_2") (pintype "passive"))
    )
    (net (code "91") (name "unconnected-(X1-Pad5)") (class "Default")
      (node (ref "X1") (pin "5") (pinfunction "5_5") (pintype "passive"))
    )
    (net (code "92") (name "unconnected-(X1-PadS1)") (class "Default")
      (node (ref "X1") (pin "S1") (pinfunction "S1_S1") (pintype "passive"))
    )
    (net (code "93") (name "unconnected-(X1-PadS2)") (class "Default")
      (node (ref "X1") (pin "S2") (pinfunction "S2_S2") (pintype "passive"))
    )
  )
)
